# MotorControl.net
KiCad netlist of a schematic drawn in Altium Designer
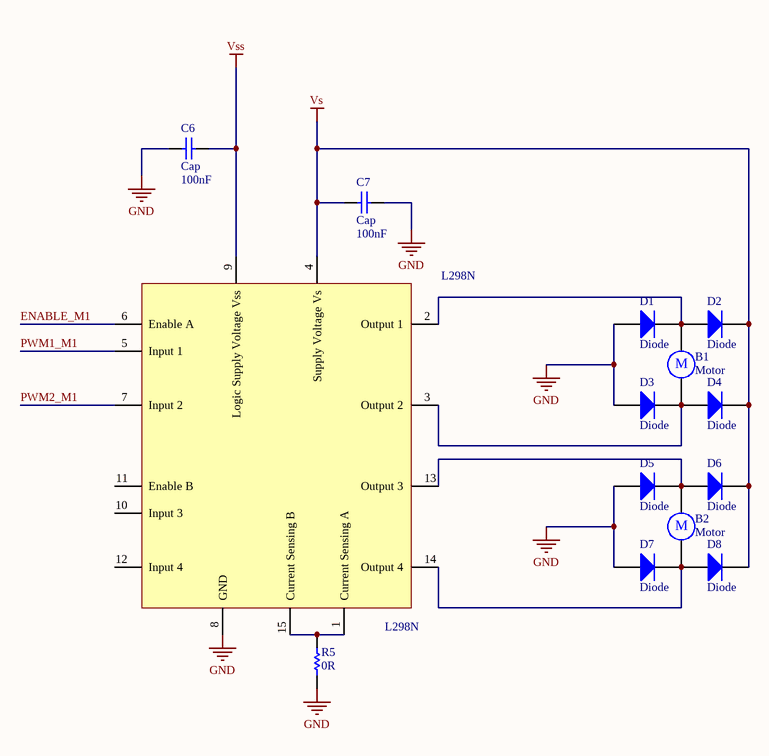
[diagram p0: MotorControl.SchDoc]

(export (version "E")
  (design (tool "Eeschema 10.0.6"))
  (components
    (comp (ref "B1")
      (value "Motor")
      (footprint "RB5-10.5")
      (description "Motor, General Kind")
      (fields (field (name "PUBLISHER") "Altium Limited"))
      (libsource (lib "Miscellaneous Devices") (part "Motor"))
    )
    (comp (ref "B2")
      (value "Motor")
      (footprint "RB5-10.5")
      (description "Motor, General Kind")
      (fields (field (name "PUBLISHER") "Altium Limited"))
      (libsource (lib "Miscellaneous Devices") (part "Motor"))
    )
    (comp (ref "C6")
      (value "Cap")
      (footprint "RAD-0.3")
      (description "Capacitor")
      (fields (field (name "ALTIUM_VALUE") "100nF") (field (name "PUBLISHER") "Altium Limited"))
      (libsource (lib "Miscellaneous Devices") (part "Cap"))
    )
    (comp (ref "C7")
      (value "Cap")
      (footprint "RAD-0.3")
      (description "Capacitor")
      (fields (field (name "ALTIUM_VALUE") "100nF") (field (name "PUBLISHER") "Altium Limited"))
      (libsource (lib "Miscellaneous Devices") (part "Cap"))
    )
    (comp (ref "D1")
      (value "Diode")
      (footprint "SMC")
      (description "Default Diode")
      (fields (field (name "PUBLISHER") "Altium Limited"))
      (libsource (lib "Miscellaneous Devices") (part "Diode"))
    )
    (comp (ref "D2")
      (value "Diode")
      (footprint "SMC")
      (description "Default Diode")
      (fields (field (name "PUBLISHER") "Altium Limited"))
      (libsource (lib "Miscellaneous Devices") (part "Diode"))
    )
    (comp (ref "D3")
      (value "Diode")
      (footprint "SMC")
      (description "Default Diode")
      (fields (field (name "PUBLISHER") "Altium Limited"))
      (libsource (lib "Miscellaneous Devices") (part "Diode"))
    )
    (comp (ref "D4")
      (value "Diode")
      (footprint "SMC")
      (description "Default Diode")
      (fields (field (name "PUBLISHER") "Altium Limited"))
      (libsource (lib "Miscellaneous Devices") (part "Diode"))
    )
    (comp (ref "D5")
      (value "Diode")
      (footprint "SMC")
      (description "Default Diode")
      (fields (field (name "PUBLISHER") "Altium Limited"))
      (libsource (lib "Miscellaneous Devices") (part "Diode"))
    )
    (comp (ref "D6")
      (value "Diode")
      (footprint "SMC")
      (description "Default Diode")
      (fields (field (name "PUBLISHER") "Altium Limited"))
      (libsource (lib "Miscellaneous Devices") (part "Diode"))
    )
    (comp (ref "D7")
      (value "Diode")
      (footprint "SMC")
      (description "Default Diode")
      (fields (field (name "PUBLISHER") "Altium Limited"))
      (libsource (lib "Miscellaneous Devices") (part "Diode"))
    )
    (comp (ref "D8")
      (value "Diode")
      (footprint "SMC")
      (description "Default Diode")
      (fields (field (name "PUBLISHER") "Altium Limited"))
      (libsource (lib "Miscellaneous Devices") (part "Diode"))
    )
    (comp (ref "L298N") (value "L298N") (footprint "L298N") (libsource (lib "SCHLIB_Autobot") (part "L298N")))
    (comp (ref "R5")
      (value "0R")
      (footprint "AXIAL-0.3")
      (description "Resistor")
      (fields (field (name "PUBLISHER") "Altium Limited"))
      (libsource (lib "Miscellaneous Devices") (part "Res1"))
    )
  )
  (nets
    (net (code "1") (name "/ENABLE_M1") (class "Default")
      (node (ref "L298N") (pin "6") (pinfunction "Enable_A_6") (pintype "passive"))
    )
    (net (code "2") (name "/PWM1_M1") (class "Default")
      (node (ref "L298N") (pin "5") (pinfunction "Input_1_5") (pintype "passive"))
    )
    (net (code "3") (name "/PWM2_M1") (class "Default")
      (node (ref "L298N") (pin "7") (pinfunction "Input_2_7") (pintype "passive"))
    )
    (net (code "4") (name "GND") (class "Default")
      (node (ref "C6") (pin "2") (pinfunction "2_2") (pintype "passive"))
      (node (ref "C7") (pin "2") (pinfunction "2_2") (pintype "passive"))
      (node (ref "D1") (pin "1") (pinfunction "A_1") (pintype "passive"))
      (node (ref "D3") (pin "1") (pinfunction "A_1") (pintype "passive"))
      (node (ref "D5") (pin "1") (pinfunction "A_1") (pintype "passive"))
      (node (ref "D7") (pin "1") (pinfunction "A_1") (pintype "passive"))
      (node (ref "L298N") (pin "8") (pinfunction "GND_8") (pintype "passive"))
      (node (ref "R5") (pin "1") (pinfunction "1_1") (pintype "passive"))
    )
    (net (code "5") (name "Net-(D1-K)") (class "Default")
      (node (ref "B1") (pin "1") (pinfunction "1_1") (pintype "passive"))
      (node (ref "D1") (pin "2") (pinfunction "K_2") (pintype "passive"))
      (node (ref "D2") (pin "1") (pinfunction "A_1") (pintype "passive"))
      (node (ref "L298N") (pin "2") (pinfunction "Output_1_2") (pintype "passive"))
    )
    (net (code "6") (name "Net-(D3-K)") (class "Default")
      (node (ref "B1") (pin "2") (pinfunction "2_2") (pintype "passive"))
      (node (ref "D3") (pin "2") (pinfunction "K_2") (pintype "passive"))
      (node (ref "D4") (pin "1") (pinfunction "A_1") (pintype "passive"))
      (node (ref "L298N") (pin "3") (pinfunction "Output_2_3") (pintype "passive"))
    )
    (net (code "7") (name "Net-(D5-K)") (class "Default")
      (node (ref "B2") (pin "1") (pinfunction "1_1") (pintype "passive"))
      (node (ref "D5") (pin "2") (pinfunction "K_2") (pintype "passive"))
      (node (ref "D6") (pin "1") (pinfunction "A_1") (pintype "passive"))
      (node (ref "L298N") (pin "13") (pinfunction "Output_3_13") (pintype "passive"))
    )
    (net (code "8") (name "Net-(D7-K)") (class "Default")
      (node (ref "B2") (pin "2") (pinfunction "2_2") (pintype "passive"))
      (node (ref "D7") (pin "2") (pinfunction "K_2") (pintype "passive"))
      (node (ref "D8") (pin "1") (pinfunction "A_1") (pintype "passive"))
      (node (ref "L298N") (pin "14") (pinfunction "Output_4_14") (pintype "passive"))
    )
    (net (code "9") (name "Net-(L298N-Current_Sensing_A)") (class "Default")
      (node (ref "L298N") (pin "1") (pinfunction "Current_Sensing_A_1") (pintype "passive"))
      (node (ref "L298N") (pin "15") (pinfunction "Current_Sensing_B_15") (pintype "passive"))
      (node (ref "R5") (pin "2") (pinfunction "2_2") (pintype "passive"))
    )
    (net (code "10") (name "Vs") (class "Default")
      (node (ref "C7") (pin "1") (pinfunction "1_1") (pintype "passive"))
      (node (ref "D2") (pin "2") (pinfunction "K_2") (pintype "passive"))
      (node (ref "D4") (pin "2") (pinfunction "K_2") (pintype "passive"))
      (node (ref "D6") (pin "2") (pinfunction "K_2") (pintype "passive"))
      (node (ref "D8") (pin "2") (pinfunction "K_2") (pintype "passive"))
      (node (ref "L298N") (pin "4") (pinfunction "Supply_Voltage_Vs_4") (pintype "passive"))
    )
    (net (code "11") (name "Vss") (class "Default")
      (node (ref "C6") (pin "1") (pinfunction "1_1") (pintype "passive"))
      (node (ref "L298N") (pin "9") (pinfunction "Logic_Supply_Voltage_Vss_9") (pintype "passive"))
    )
    (net (code "12") (name "unconnected-(L298N-Enable_B-Pad11)") (class "Default")
      (node (ref "L298N") (pin "11") (pinfunction "Enable_B_11") (pintype "passive"))
    )
    (net (code "13") (name "unconnected-(L298N-Input_3-Pad10)") (class "Default")
      (node (ref "L298N") (pin "10") (pinfunction "Input_3_10") (pintype "passive"))
    )
    (net (code "14") (name "unconnected-(L298N-Input_4-Pad12)") (class "Default")
      (node (ref "L298N") (pin "12") (pinfunction "Input_4_12") (pintype "passive"))
    )
  )
)
